# Front_right_lamp_v5.net
KiCad netlist of a schematic drawn in EAGLE
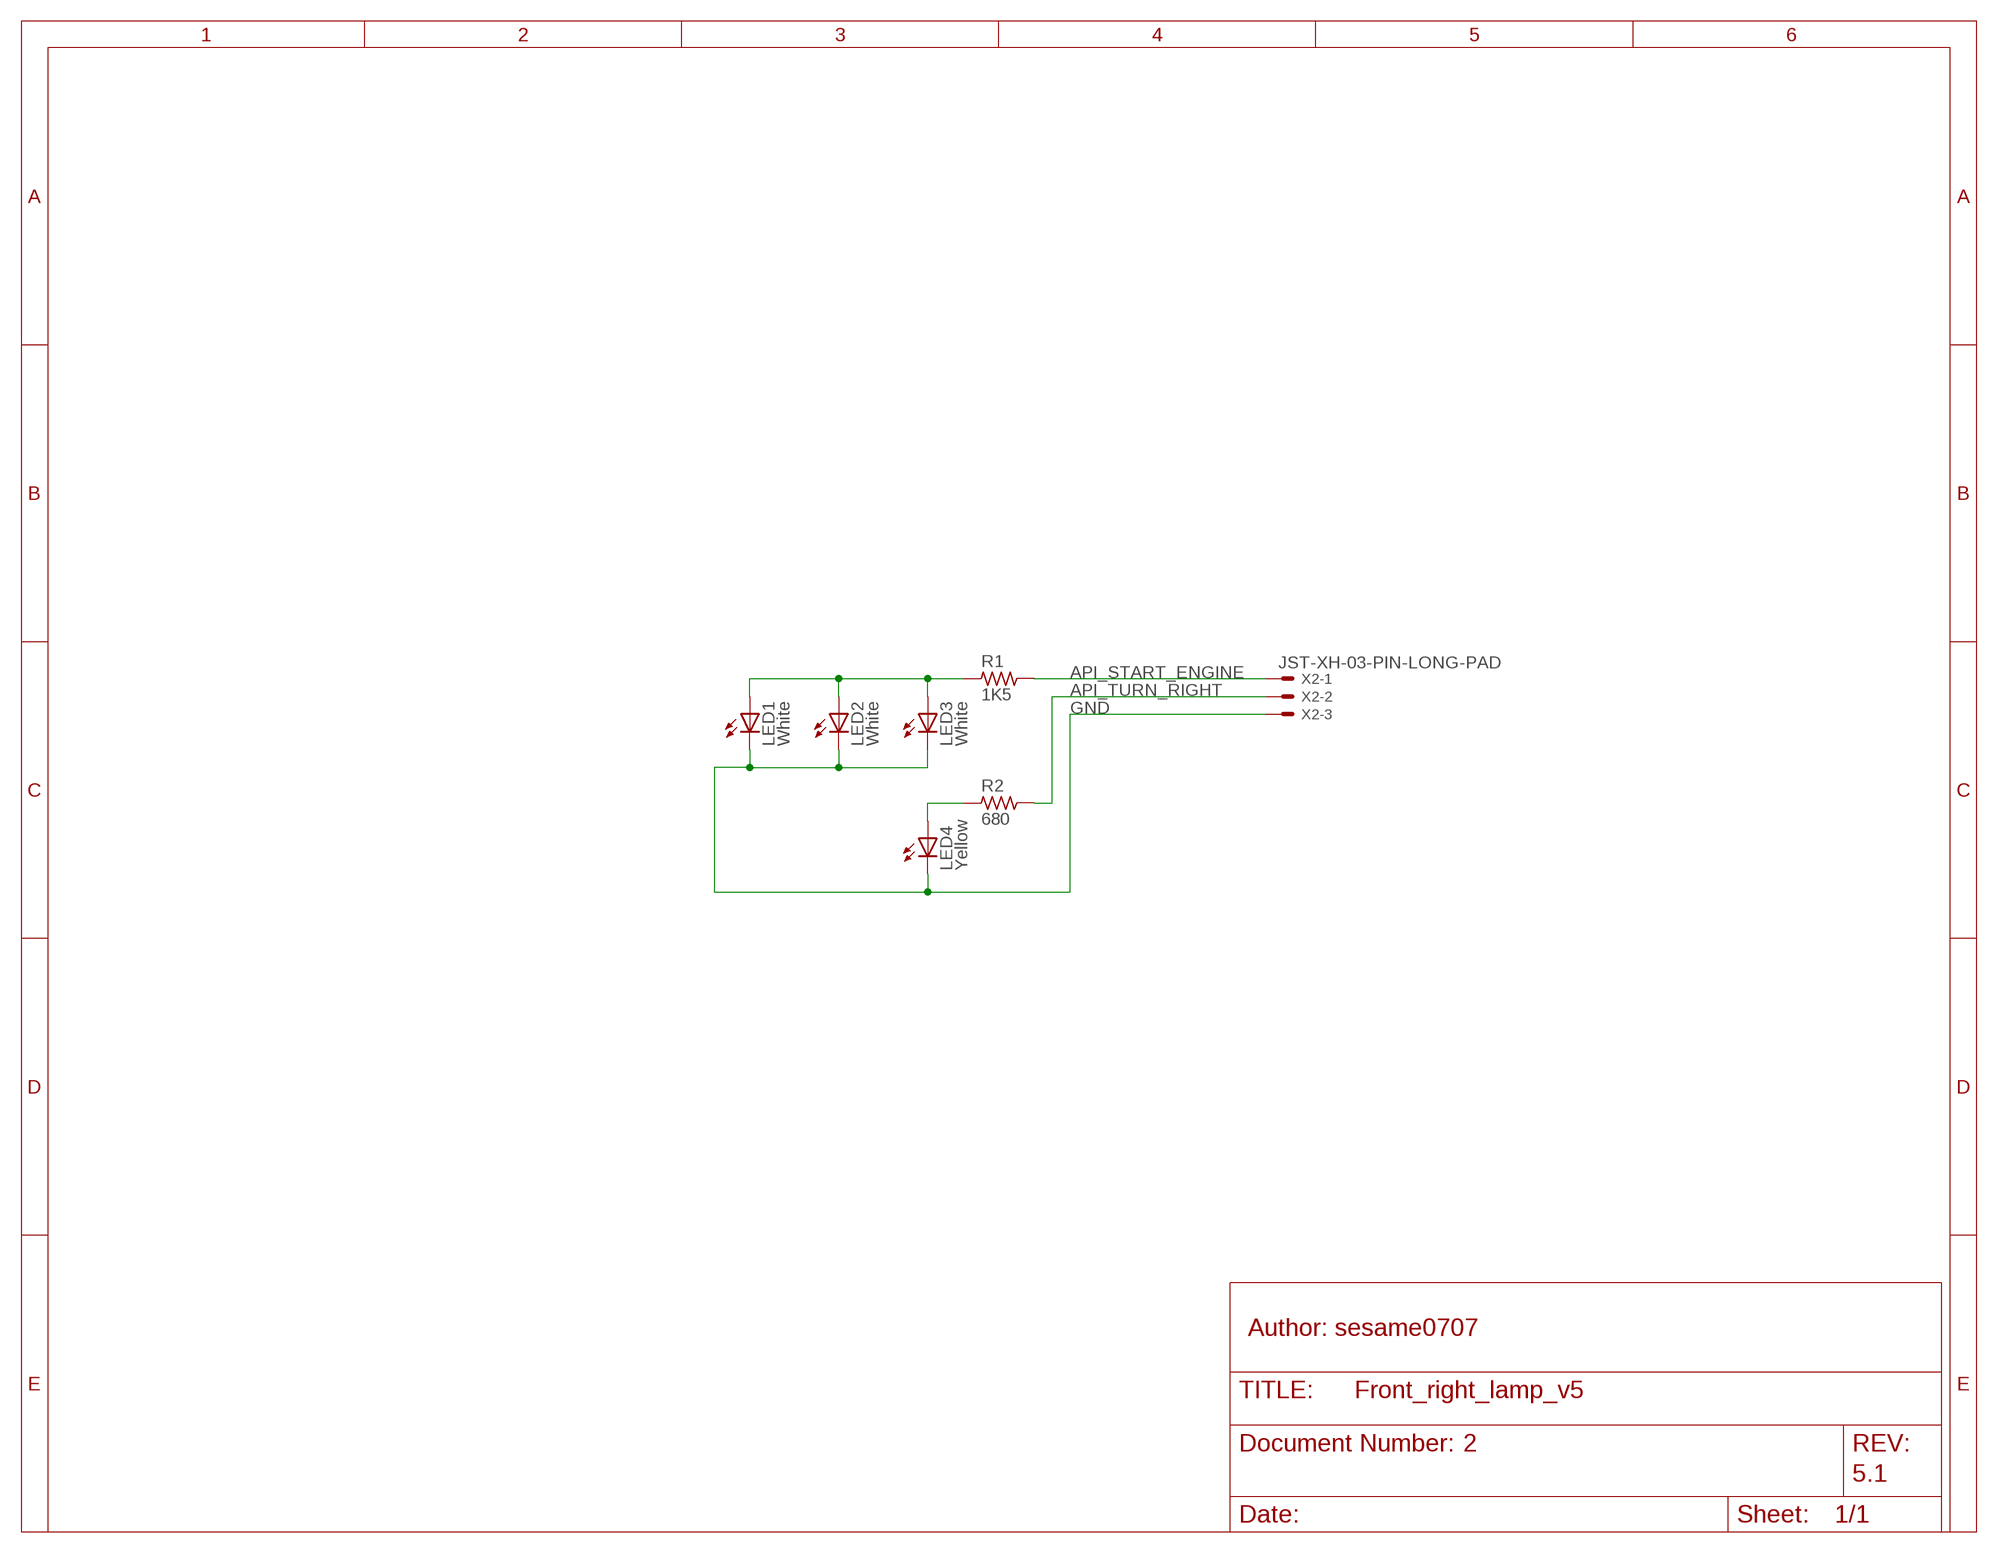
[diagram p0: schematic, sheet 1]

(export (version "E")
  (design (tool "Eeschema 10.0.6"))
  (components
    (comp (ref "LED1")
      (value "White")
      (footprint "eagle-import:LED5MM")
      (fields
        (field (name "MANUFACTURER") "LUCKYLIGHT")
        (field (name "MANUFACTURER_PART_NUMBER") "LL-504WC2V-W2-3PD")
      )
      (libsource (lib "eagle-import") (part "LED5MM"))
    )
    (comp (ref "LED2")
      (value "White")
      (footprint "eagle-import:LED5MM")
      (fields
        (field (name "MANUFACTURER") "LUCKYLIGHT")
        (field (name "MANUFACTURER_PART_NUMBER") "LL-504WC2V-W2-3PD")
      )
      (libsource (lib "eagle-import") (part "LED5MM"))
    )
    (comp (ref "LED3")
      (value "White")
      (footprint "eagle-import:LED5MM")
      (fields
        (field (name "MANUFACTURER") "LUCKYLIGHT")
        (field (name "MANUFACTURER_PART_NUMBER") "LL-504WC2V-W2-3PD")
      )
      (libsource (lib "eagle-import") (part "LED5MM"))
    )
    (comp (ref "LED4")
      (value "Yellow")
      (footprint "eagle-import:LED5MM")
      (fields
        (field (name "MANUFACTURER") "LUCKYLIGHT")
        (field (name "MANUFACTURER_PART_NUMBER") "LL-503YD2E-1B")
      )
      (libsource (lib "eagle-import") (part "LED5MM"))
    )
    (comp (ref "R1")
      (value "1K5")
      (footprint "eagle-import:R1206")
      (fields
        (field (name "MANUFACTURER") "ROYAL OHM")
        (field (name "MANUFACTURER_PART_NUMBER") "1206S4J0152T5E")
      )
      (libsource (lib "eagle-import") (part "R_1206"))
    )
    (comp (ref "R2")
      (value "680")
      (footprint "eagle-import:R1206")
      (fields
        (field (name "MANUFACTURER") "ROYAL OHM")
        (field (name "MANUFACTURER_PART_NUMBER") "1206S4J0681T5E")
      )
      (libsource (lib "eagle-import") (part "R_1206"))
    )
    (comp (ref "X2")
      (value "JST-XH-03-PIN-LONG-PAD")
      (footprint "eagle-import:JST-XH-03-PACKAGE-LONG-PAD")
      (libsource (lib "eagle-import") (part "JST-XH-03-PIN-LONG-PAD"))
    )
  )
  (nets
    (net (code "1") (name "/API_START_ENGINE") (class "Default")
      (node (ref "LED1") (pin "A") (pinfunction "A_A") (pintype "passive"))
      (node (ref "LED2") (pin "A") (pinfunction "A_A") (pintype "passive"))
      (node (ref "LED3") (pin "A") (pinfunction "A_A") (pintype "passive"))
      (node (ref "R1") (pin "1") (pinfunction "1_1") (pintype "passive"))
    )
    (net (code "2") (name "/API_TURN_RIGHT") (class "Default")
      (node (ref "R2") (pin "2") (pinfunction "2_2") (pintype "passive"))
      (node (ref "X2") (pin "2") (pinfunction "S_2") (pintype "passive"))
    )
    (net (code "3") (name "/GND") (class "Default")
      (node (ref "LED1") (pin "K") (pinfunction "C_K") (pintype "passive"))
      (node (ref "LED2") (pin "K") (pinfunction "C_K") (pintype "passive"))
      (node (ref "LED3") (pin "K") (pinfunction "C_K") (pintype "passive"))
      (node (ref "LED4") (pin "K") (pinfunction "C_K") (pintype "passive"))
      (node (ref "X2") (pin "3") (pinfunction "S_3") (pintype "passive"))
    )
    (net (code "4") (name "Net-(LED4-PadA)") (class "Default")
      (node (ref "LED4") (pin "A") (pinfunction "A_A") (pintype "passive"))
      (node (ref "R2") (pin "1") (pinfunction "1_1") (pintype "passive"))
    )
    (net (code "5") (name "Net-(X2A-S)") (class "Default")
      (node (ref "R1") (pin "2") (pinfunction "2_2") (pintype "passive"))
      (node (ref "X2") (pin "1") (pinfunction "S_1") (pintype "passive"))
    )
  )
)
